# KVMeter-V2603-6_0.net
KiCad netlist of a schematic drawn in EAGLE
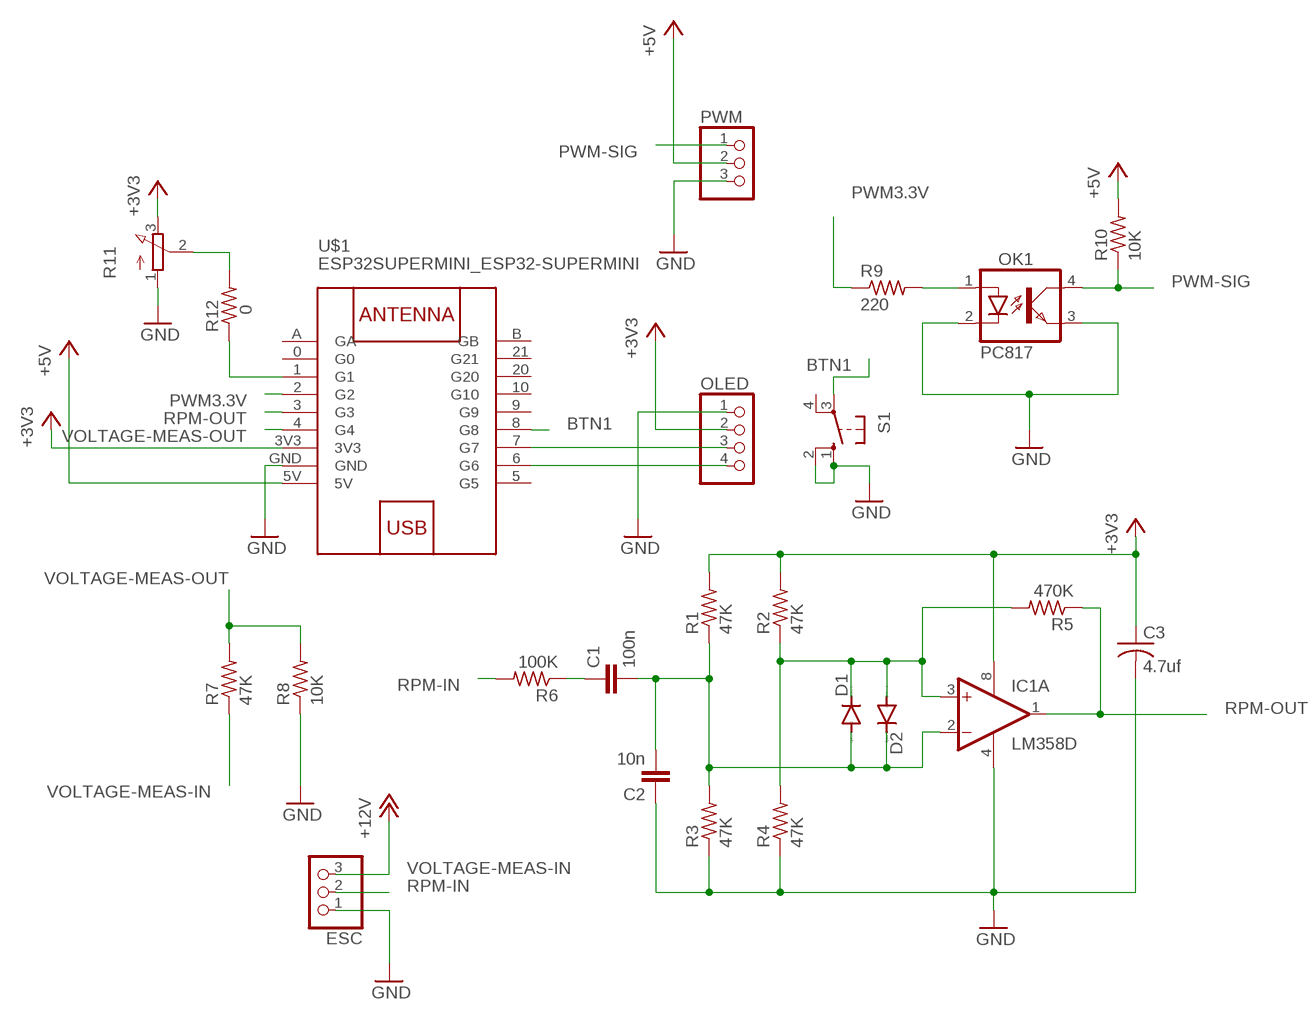
[diagram p0: schematic, sheet 1]

(export (version "E")
  (design (tool "Eeschema 10.0.6"))
  (components
    (comp (ref "C1")
      (value "100n")
      (footprint "eagle-import:C1206")
      (libsource (lib "eagle-import") (part "C-EUC1206"))
    )
    (comp (ref "C2")
      (value "10n")
      (footprint "eagle-import:C1206")
      (libsource (lib "eagle-import") (part "C-EUC1206"))
    )
    (comp (ref "C3")
      (value "4.7uf")
      (footprint "eagle-import:C1206")
      (libsource (lib "eagle-import") (part "C-USC1206"))
    )
    (comp (ref "D1")
      (value "DIODE-SOD123")
      (footprint "eagle-import:SOD123")
      (libsource (lib "eagle-import") (part "DIODE-SOD123"))
    )
    (comp (ref "D2")
      (value "DIODE-SOD123")
      (footprint "eagle-import:SOD123")
      (libsource (lib "eagle-import") (part "DIODE-SOD123"))
    )
    (comp (ref "ESC")
      (value "PINHD-1X3")
      (footprint "eagle-import:1X03")
      (libsource (lib "eagle-import") (part "PINHD-1X3"))
    )
    (comp (ref "IC1")
      (value "LM358D")
      (footprint "eagle-import:SO08")
      (libsource (lib "eagle-import") (part "LM358D"))
    )
    (comp (ref "OK1")
      (value "PC817")
      (footprint "eagle-import:DIL04")
      (fields (field (name "MPN") "PC817X4J000F"))
      (libsource (lib "eagle-import") (part "PC817"))
    )
    (comp (ref "OLED")
      (value "PINHD-1X4")
      (footprint "eagle-import:1X04")
      (libsource (lib "eagle-import") (part "PINHD-1X4"))
    )
    (comp (ref "PWM")
      (value "PINHD-1X3")
      (footprint "eagle-import:1X03")
      (libsource (lib "eagle-import") (part "PINHD-1X3"))
    )
    (comp (ref "R1")
      (value "47K")
      (footprint "eagle-import:R1206")
      (libsource (lib "eagle-import") (part "R-US_R1206"))
    )
    (comp (ref "R2")
      (value "47K")
      (footprint "eagle-import:R1206")
      (libsource (lib "eagle-import") (part "R-US_R1206"))
    )
    (comp (ref "R3")
      (value "47K")
      (footprint "eagle-import:R1206")
      (libsource (lib "eagle-import") (part "R-US_R1206"))
    )
    (comp (ref "R4")
      (value "47K")
      (footprint "eagle-import:R1206")
      (libsource (lib "eagle-import") (part "R-US_R1206"))
    )
    (comp (ref "R5")
      (value "470K")
      (footprint "eagle-import:R1206")
      (libsource (lib "eagle-import") (part "R-US_R1206"))
    )
    (comp (ref "R6")
      (value "100K")
      (footprint "eagle-import:R1206")
      (libsource (lib "eagle-import") (part "R-US_R1206"))
    )
    (comp (ref "R7")
      (value "47K")
      (footprint "eagle-import:R1206")
      (libsource (lib "eagle-import") (part "R-US_R1206"))
    )
    (comp (ref "R8")
      (value "10K")
      (footprint "eagle-import:R1206")
      (libsource (lib "eagle-import") (part "R-US_R1206"))
    )
    (comp (ref "R9")
      (value "220")
      (footprint "eagle-import:R1206")
      (libsource (lib "eagle-import") (part "R-US_R1206"))
    )
    (comp (ref "R10")
      (value "10K")
      (footprint "eagle-import:R1206")
      (libsource (lib "eagle-import") (part "R-US_R1206"))
    )
    (comp (ref "R11")
      (value "3RP/1610N")
      (footprint "eagle-import:3RP_1610N")
      (libsource (lib "eagle-import") (part "3RP/1610N"))
    )
    (comp (ref "R12")
      (value "0")
      (footprint "eagle-import:R1206")
      (libsource (lib "eagle-import") (part "R-US_R1206"))
    )
    (comp (ref "S1")
      (value "10-XX")
      (footprint "eagle-import:B3F-10XX")
      (fields (field (name "MPN") "B3F-1000"))
      (libsource (lib "eagle-import") (part "10-XX"))
    )
    (comp (ref "U$1")
      (value "ESP32SUPERMINI_ESP32-SUPERMINI")
      (footprint "eagle-import:ESP32SUPERMINI_ESP32-SUPERMINI")
      (libsource (lib "eagle-import") (part "ESP32SUPERMINI_ESP32-SUPERMINI"))
    )
  )
  (nets
    (net (code "1") (name "+3V3") (class "Default")
      (node (ref "C3") (pin "1") (pinfunction "1_1") (pintype "passive"))
      (node (ref "IC1") (pin "8") (pinfunction "V+_8") (pintype "power_in"))
      (node (ref "OLED") (pin "2") (pinfunction "2_2") (pintype "passive"))
      (node (ref "R1") (pin "2") (pinfunction "2_2") (pintype "passive"))
      (node (ref "R11") (pin "3") (pinfunction "E_3") (pintype "passive"))
      (node (ref "R2") (pin "2") (pinfunction "2_2") (pintype "passive"))
      (node (ref "U$1") (pin "3V3") (pinfunction "3V3_3V3") (pintype "power_in"))
    )
    (net (code "2") (name "+5V") (class "Default")
      (node (ref "PWM") (pin "2") (pinfunction "2_2") (pintype "passive"))
      (node (ref "R10") (pin "2") (pinfunction "2_2") (pintype "passive"))
      (node (ref "U$1") (pin "5V") (pinfunction "5V_5V") (pintype "power_in"))
    )
    (net (code "3") (name "+12V") (class "Default")
      (node (ref "ESC") (pin "3") (pinfunction "3_3") (pintype "passive"))
      (node (ref "R7") (pin "1") (pinfunction "1_1") (pintype "passive"))
    )
    (net (code "4") (name "/BTN1") (class "Default")
      (node (ref "S1") (pin "3") (pinfunction "P_3") (pintype "passive"))
      (node (ref "U$1") (pin "8") (pinfunction "G8_8") (pintype "bidirectional"))
    )
    (net (code "5") (name "/PWM-SIG") (class "Default")
      (node (ref "OK1") (pin "4") (pinfunction "COL_4") (pintype "passive"))
      (node (ref "PWM") (pin "1") (pinfunction "1_1") (pintype "passive"))
      (node (ref "R10") (pin "1") (pinfunction "1_1") (pintype "passive"))
    )
    (net (code "6") (name "/PWM3.3V") (class "Default")
      (node (ref "R9") (pin "1") (pinfunction "1_1") (pintype "passive"))
      (node (ref "U$1") (pin "2") (pinfunction "G2_2") (pintype "bidirectional"))
    )
    (net (code "7") (name "/RPM-IN") (class "Default")
      (node (ref "ESC") (pin "2") (pinfunction "2_2") (pintype "passive"))
      (node (ref "R6") (pin "2") (pinfunction "2_2") (pintype "passive"))
    )
    (net (code "8") (name "/RPM-OUT") (class "Default")
      (node (ref "IC1") (pin "1") (pinfunction "OUT_1") (pintype "output"))
      (node (ref "R5") (pin "1") (pinfunction "1_1") (pintype "passive"))
      (node (ref "U$1") (pin "3") (pinfunction "G3_3") (pintype "bidirectional"))
    )
    (net (code "9") (name "/VOLTAGE-MEAS-OUT") (class "Default")
      (node (ref "R7") (pin "2") (pinfunction "2_2") (pintype "passive"))
      (node (ref "R8") (pin "2") (pinfunction "2_2") (pintype "passive"))
      (node (ref "U$1") (pin "4") (pinfunction "G4_4") (pintype "bidirectional"))
    )
    (net (code "10") (name "GND") (class "Default")
      (node (ref "C2") (pin "1") (pinfunction "1_1") (pintype "passive"))
      (node (ref "C3") (pin "2") (pinfunction "2_2") (pintype "passive"))
      (node (ref "ESC") (pin "1") (pinfunction "1_1") (pintype "passive"))
      (node (ref "IC1") (pin "4") (pinfunction "V-_4") (pintype "power_in"))
      (node (ref "OK1") (pin "2") (pinfunction "C_2") (pintype "passive"))
      (node (ref "OK1") (pin "3") (pinfunction "EMIT_3") (pintype "passive"))
      (node (ref "OLED") (pin "1") (pinfunction "1_1") (pintype "passive"))
      (node (ref "PWM") (pin "3") (pinfunction "3_3") (pintype "passive"))
      (node (ref "R11") (pin "1") (pinfunction "A_1") (pintype "passive"))
      (node (ref "R3") (pin "1") (pinfunction "1_1") (pintype "passive"))
      (node (ref "R4") (pin "1") (pinfunction "1_1") (pintype "passive"))
      (node (ref "R8") (pin "1") (pinfunction "1_1") (pintype "passive"))
      (node (ref "S1") (pin "1") (pinfunction "S_1") (pintype "passive"))
      (node (ref "S1") (pin "2") (pinfunction "S1_2") (pintype "passive"))
      (node (ref "U$1") (pin "GND") (pinfunction "GND_GND") (pintype "power_in"))
    )
    (net (code "11") (name "Net-(C1-Pad1)") (class "Default")
      (node (ref "C1") (pin "1") (pinfunction "1_1") (pintype "passive"))
      (node (ref "R6") (pin "1") (pinfunction "1_1") (pintype "passive"))
    )
    (net (code "12") (name "Net-(IC1A-+IN)") (class "Default")
      (node (ref "D1") (pin "C") (pinfunction "C_C") (pintype "passive"))
      (node (ref "D2") (pin "A") (pinfunction "A_A") (pintype "passive"))
      (node (ref "IC1") (pin "3") (pinfunction "+IN_3") (pintype "input"))
      (node (ref "R2") (pin "1") (pinfunction "1_1") (pintype "passive"))
      (node (ref "R4") (pin "2") (pinfunction "2_2") (pintype "passive"))
      (node (ref "R5") (pin "2") (pinfunction "2_2") (pintype "passive"))
    )
    (net (code "13") (name "Net-(IC1A--IN)") (class "Default")
      (node (ref "C1") (pin "2") (pinfunction "2_2") (pintype "passive"))
      (node (ref "C2") (pin "2") (pinfunction "2_2") (pintype "passive"))
      (node (ref "D1") (pin "A") (pinfunction "A_A") (pintype "passive"))
      (node (ref "D2") (pin "C") (pinfunction "C_C") (pintype "passive"))
      (node (ref "IC1") (pin "2") (pinfunction "-IN_2") (pintype "input"))
      (node (ref "R1") (pin "1") (pinfunction "1_1") (pintype "passive"))
      (node (ref "R3") (pin "2") (pinfunction "2_2") (pintype "passive"))
    )
    (net (code "14") (name "Net-(OK1-A)") (class "Default")
      (node (ref "OK1") (pin "1") (pinfunction "A_1") (pintype "passive"))
      (node (ref "R9") (pin "2") (pinfunction "2_2") (pintype "passive"))
    )
    (net (code "15") (name "Net-(R11-S)") (class "Default")
      (node (ref "R11") (pin "2") (pinfunction "S_2") (pintype "passive"))
      (node (ref "R12") (pin "2") (pinfunction "2_2") (pintype "passive"))
    )
    (net (code "16") (name "Net-(U$1-G1)") (class "Default")
      (node (ref "R12") (pin "1") (pinfunction "1_1") (pintype "passive"))
      (node (ref "U$1") (pin "1") (pinfunction "G1_1") (pintype "bidirectional"))
    )
    (net (code "17") (name "Net-(U$1-G6)") (class "Default")
      (node (ref "OLED") (pin "4") (pinfunction "4_4") (pintype "passive"))
      (node (ref "U$1") (pin "6") (pinfunction "G6_6") (pintype "bidirectional"))
    )
    (net (code "18") (name "Net-(U$1-G7)") (class "Default")
      (node (ref "OLED") (pin "3") (pinfunction "3_3") (pintype "passive"))
      (node (ref "U$1") (pin "7") (pinfunction "G7_7") (pintype "bidirectional"))
    )
    (net (code "19") (name "unconnected-(S1-P1-Pad4)") (class "Default")
      (node (ref "S1") (pin "4") (pinfunction "P1_4") (pintype "passive"))
    )
    (net (code "20") (name "unconnected-(U$1-G0-Pad0)") (class "Default")
      (node (ref "U$1") (pin "0") (pinfunction "G0_0") (pintype "bidirectional"))
    )
    (net (code "21") (name "unconnected-(U$1-G5-Pad5)") (class "Default")
      (node (ref "U$1") (pin "5") (pinfunction "G5_5") (pintype "bidirectional"))
    )
    (net (code "22") (name "unconnected-(U$1-G9-Pad9)") (class "Default")
      (node (ref "U$1") (pin "9") (pinfunction "G9_9") (pintype "bidirectional"))
    )
    (net (code "23") (name "unconnected-(U$1-G10-Pad10)") (class "Default")
      (node (ref "U$1") (pin "10") (pinfunction "G10_10") (pintype "bidirectional"))
    )
    (net (code "24") (name "unconnected-(U$1-G20-Pad20)") (class "Default")
      (node (ref "U$1") (pin "20") (pinfunction "G20_20") (pintype "bidirectional"))
    )
    (net (code "25") (name "unconnected-(U$1-G21-Pad21)") (class "Default")
      (node (ref "U$1") (pin "21") (pinfunction "G21_21") (pintype "bidirectional"))
    )
    (net (code "26") (name "unconnected-(U$1-GA-PadA)") (class "Default")
      (node (ref "U$1") (pin "A") (pinfunction "GA_A") (pintype "bidirectional"))
    )
    (net (code "27") (name "unconnected-(U$1-GB-PadB)") (class "Default")
      (node (ref "U$1") (pin "B") (pinfunction "GB_B") (pintype "bidirectional"))
    )
  )
)
